# thermocouple.net
KiCad netlist of a schematic drawn in Altium Designer
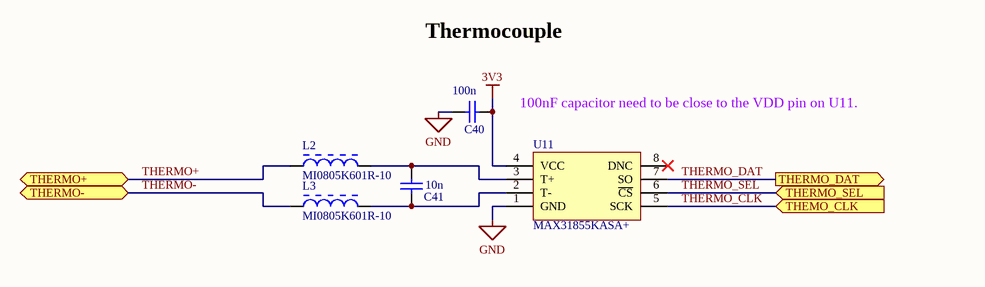
[diagram p0: thermocouple.SchDoc]

(export (version "E")
  (design (tool "Eeschema 10.0.6"))
  (components
    (comp (ref "C40")
      (value "100n")
      (footprint "0805")
      (description "Generic 0805 Capacitor")
      (libsource (lib "symbol_library") (part "C_0805"))
    )
    (comp (ref "C41")
      (value "10n")
      (footprint "0805")
      (description "Generic 0805 Capacitor")
      (libsource (lib "symbol_library") (part "C_0805"))
    )
    (comp (ref "L2")
      (value "MI0805K601R-10")
      (footprint "0805")
      (fields (field (name "MANUFACTURER") "Laird"))
      (libsource (lib "symbol_library") (part "MI0805K"))
    )
    (comp (ref "L3")
      (value "MI0805K601R-10")
      (footprint "0805")
      (fields (field (name "MANUFACTURER") "Laird"))
      (libsource (lib "symbol_library") (part "MI0805K"))
    )
    (comp (ref "U11")
      (value "MAX31855KASA+")
      (footprint "SOIC8")
      (description "Cold-Junction Compensated\r\nThermocouple-to-Digital Converter")
      (libsource (lib "symbol_library") (part "MAX31855"))
    )
  )
  (nets
    (net (code "1") (name "/THERMO+") (class "Default")
      (node (ref "L2") (pin "1") (pinfunction "1_1") (pintype "passive"))
    )
    (net (code "2") (name "/THERMO-") (class "Default")
      (node (ref "L3") (pin "1") (pinfunction "1_1") (pintype "passive"))
    )
    (net (code "3") (name "/THERMO_CLK") (class "Default")
      (node (ref "U11") (pin "5") (pinfunction "SCK_5") (pintype "passive"))
    )
    (net (code "4") (name "/THERMO_DAT") (class "Default")
      (node (ref "U11") (pin "7") (pinfunction "SO_7") (pintype "passive"))
    )
    (net (code "5") (name "/THERMO_SEL") (class "Default")
      (node (ref "U11") (pin "6") (pinfunction "~{CS}_6") (pintype "passive"))
    )
    (net (code "6") (name "3V3") (class "Default")
      (node (ref "C40") (pin "2") (pinfunction "2_2") (pintype "passive"))
      (node (ref "U11") (pin "4") (pinfunction "VCC_4") (pintype "power_in"))
    )
    (net (code "7") (name "GND") (class "Default")
      (node (ref "C40") (pin "1") (pinfunction "1_1") (pintype "passive"))
      (node (ref "U11") (pin "1") (pinfunction "GND_1") (pintype "power_in"))
    )
    (net (code "8") (name "Net-(U11-T+)") (class "Default")
      (node (ref "C41") (pin "2") (pinfunction "2_2") (pintype "passive"))
      (node (ref "L2") (pin "2") (pinfunction "2_2") (pintype "passive"))
      (node (ref "U11") (pin "3") (pinfunction "T+_3") (pintype "passive"))
    )
    (net (code "9") (name "Net-(U11-T-)") (class "Default")
      (node (ref "C41") (pin "1") (pinfunction "1_1") (pintype "passive"))
      (node (ref "L3") (pin "2") (pinfunction "2_2") (pintype "passive"))
      (node (ref "U11") (pin "2") (pinfunction "T-_2") (pintype "passive"))
    )
    (net (code "10") (name "unconnected-(U11-DNC-Pad8)") (class "Default")
      (node (ref "U11") (pin "8") (pinfunction "DNC_8") (pintype "passive+no_connect"))
    )
  )
)
